# A7_JTAG_CONFIG_-.net
KiCad netlist of a schematic drawn in Altium Designer
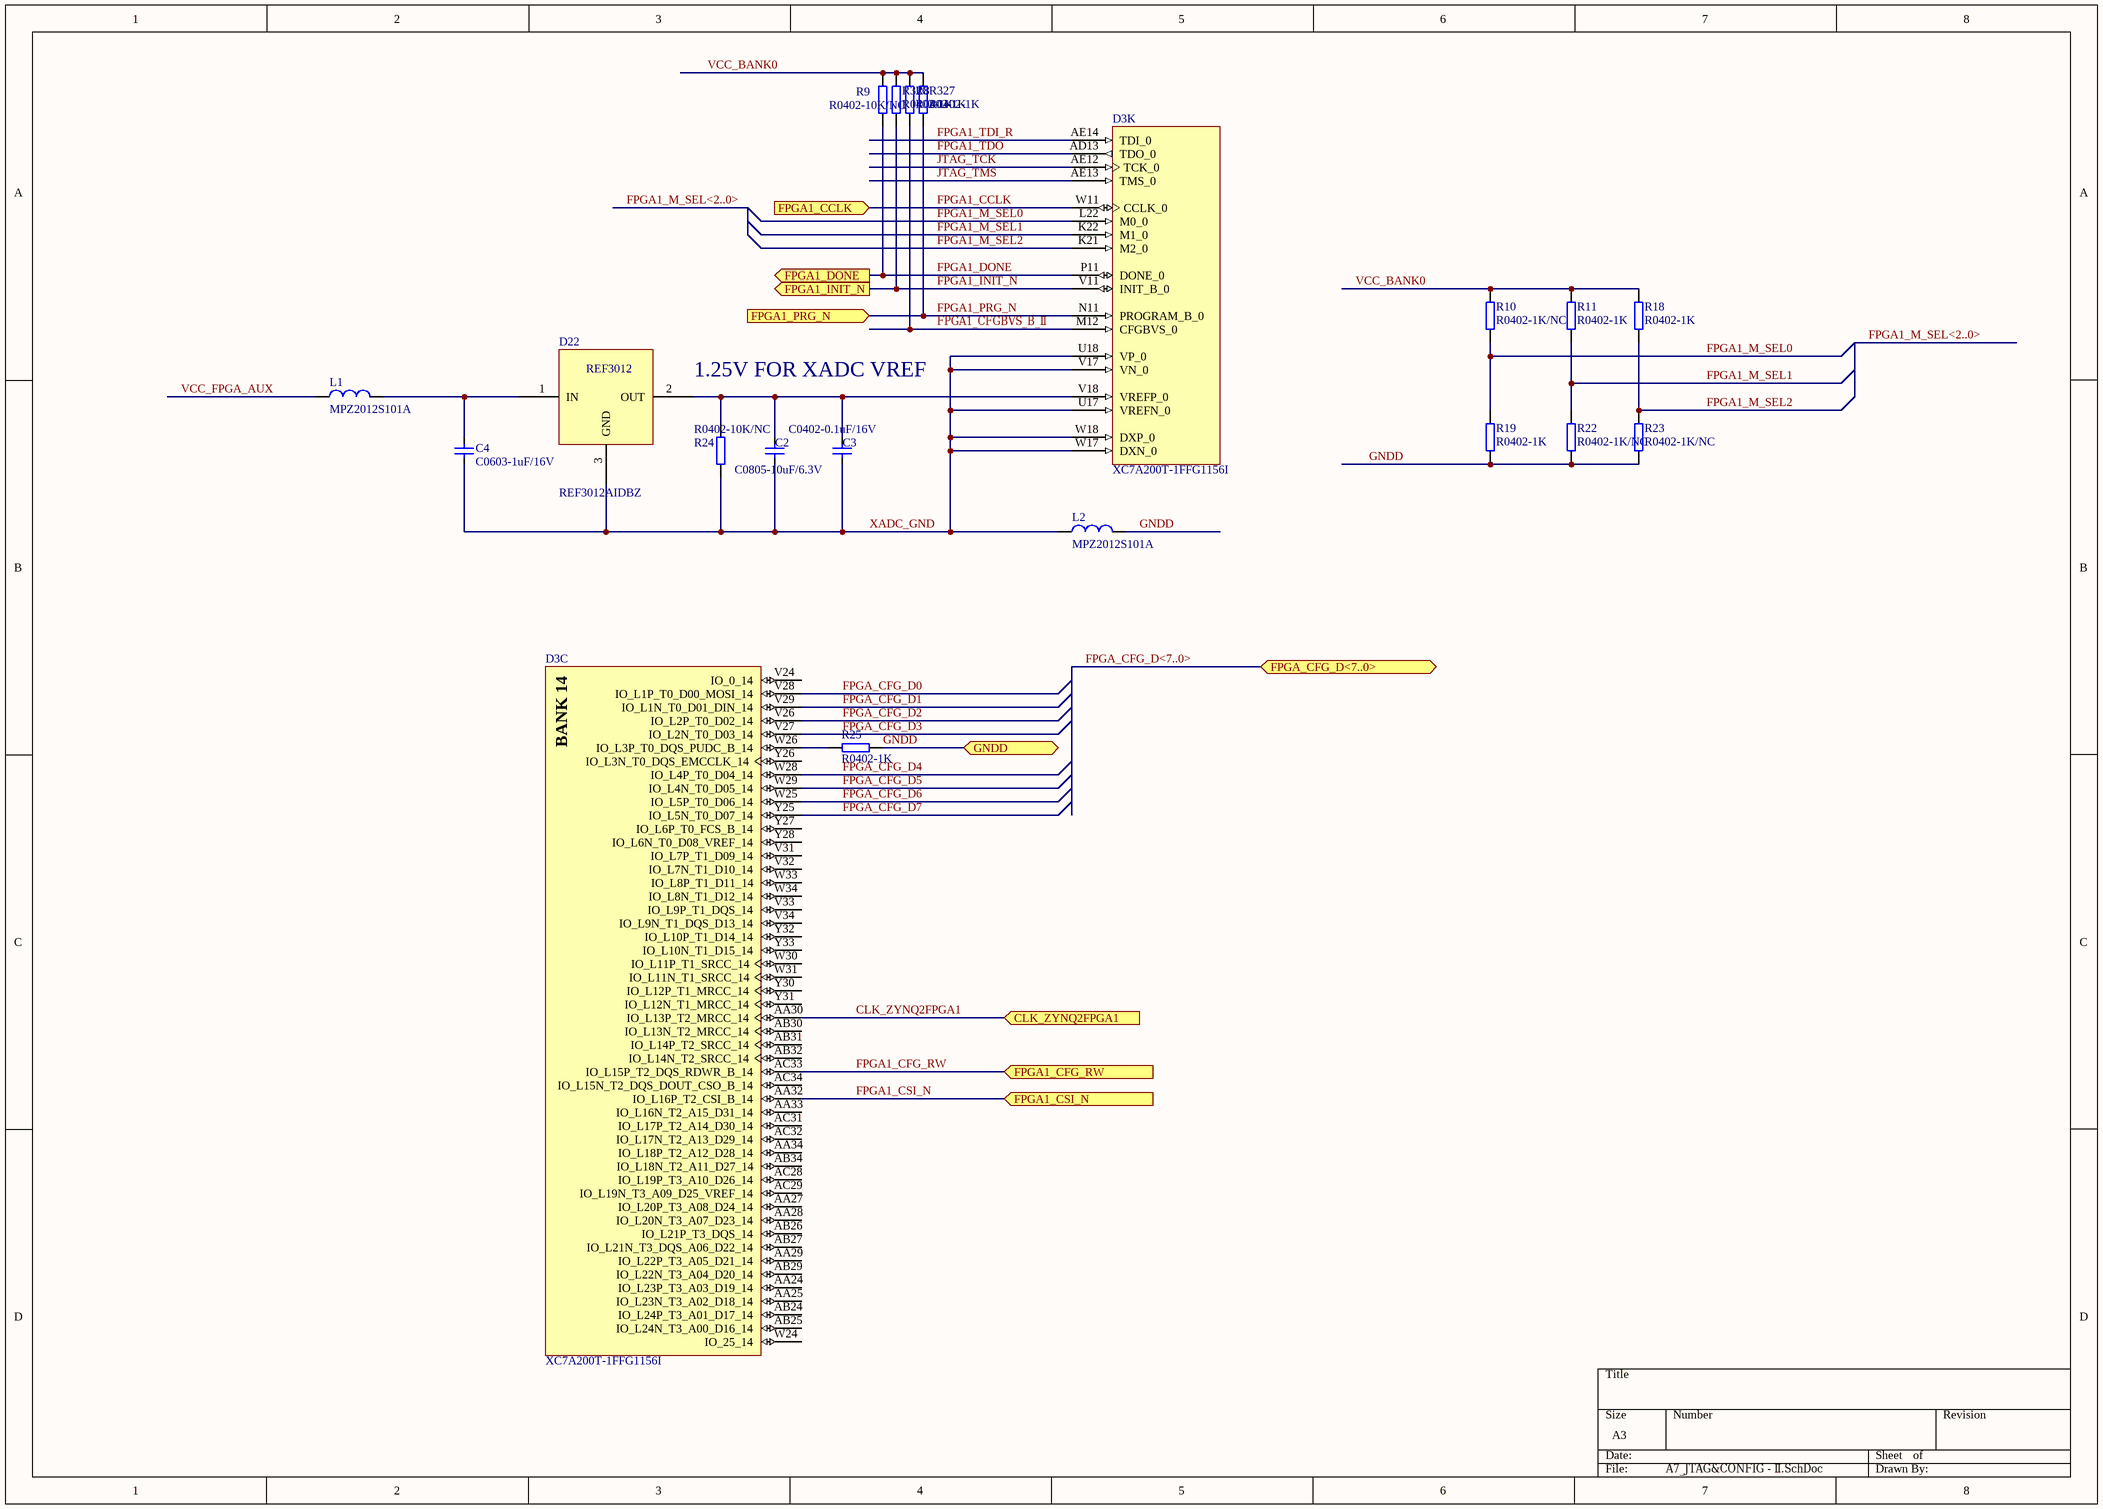
[diagram p0: A7_JTAG&CONFIG - Ⅱ.SchDoc]

(export (version "E")
  (design (tool "Eeschema 10.0.6"))
  (components
    (comp (ref "C2")
      (value "C0805-10uF/6.3V")
      (footprint "C0805")
      (fields (field (name "SCHEMATIC_PART") "CAP"))
      (libsource (lib "Database_Libs1") (part "CAP"))
    )
    (comp (ref "C3")
      (value "C0402-0.1uF/16V")
      (footprint "C0402")
      (description "X7R")
      (fields (field (name "SCHEMATIC_PART") "CAP") (field (name "MANUFACTURER") "SAMSUNG"))
      (libsource (lib "Database_Libs1") (part "CAP"))
    )
    (comp (ref "C4")
      (value "C0603-1uF/16V")
      (footprint "C0603")
      (description "X7R")
      (fields (field (name "SCHEMATIC_PART") "CAP"))
      (libsource (lib "Database_Libs1") (part "CAP"))
    )
    (comp (ref "D3")
      (value "XC7A200T-1FFG1156I")
      (footprint "FFG1156")
      (description "Artix-7 FPGA, 500 User I/Os, 16 GTP, 1156-Ball BGA, Speed Grade 1, Industrial Grade, Pb-Free")
      (fields (field (name "GENERIC PART NUMBER") "XC7A200T") (field (name "MANUFACTURER") "Xilinx"))
      (libsource (lib "Xilinx Artix-7") (part "XC7A200T-1FFG1156I"))
    )
    (comp (ref "D22")
      (value "REF3012AIDBZ")
      (footprint "SOT-23")
      (libsource (lib "SCHLIB1") (part "REF3012"))
    )
    (comp (ref "L1")
      (value "MPZ2012S101A")
      (footprint "R0805")
      (fields (field (name "SCHEMATIC_PART") "BEAD") (field (name "MANUFACTURER") "TDK"))
      (libsource (lib "Database_Libs1") (part "BEAD"))
    )
    (comp (ref "L2")
      (value "MPZ2012S101A")
      (footprint "R0805")
      (fields (field (name "SCHEMATIC_PART") "BEAD") (field (name "MANUFACTURER") "TDK"))
      (libsource (lib "Database_Libs1") (part "BEAD"))
    )
    (comp (ref "R8")
      (value "R0402-1K")
      (footprint "R0402")
      (fields (field (name "SCHEMATIC_PART") "RES") (field (name "MANUFACTURER") "SAMSUNG"))
      (libsource (lib "Database_Libs1") (part "RES"))
    )
    (comp (ref "R9")
      (value "R0402-10K/NC")
      (footprint "R0402")
      (fields (field (name "SCHEMATIC_PART") "RES") (field (name "MANUFACTURER") "SAMSUNG"))
      (libsource (lib "Database_Libs1") (part "RES"))
    )
    (comp (ref "R10")
      (value "R0402-1K/NC")
      (footprint "R0402")
      (fields (field (name "SCHEMATIC_PART") "RES") (field (name "MANUFACTURER") "SAMSUNG"))
      (libsource (lib "Database_Libs1") (part "RES"))
    )
    (comp (ref "R11")
      (value "R0402-1K")
      (footprint "R0402")
      (fields (field (name "SCHEMATIC_PART") "RES") (field (name "MANUFACTURER") "SAMSUNG"))
      (libsource (lib "Database_Libs1") (part "RES"))
    )
    (comp (ref "R18")
      (value "R0402-1K")
      (footprint "R0402")
      (fields (field (name "SCHEMATIC_PART") "RES") (field (name "MANUFACTURER") "SAMSUNG"))
      (libsource (lib "Database_Libs1") (part "RES"))
    )
    (comp (ref "R19")
      (value "R0402-1K")
      (footprint "R0402")
      (fields (field (name "SCHEMATIC_PART") "RES") (field (name "MANUFACTURER") "SAMSUNG"))
      (libsource (lib "Database_Libs1") (part "RES"))
    )
    (comp (ref "R22")
      (value "R0402-1K/NC")
      (footprint "R0402")
      (fields (field (name "SCHEMATIC_PART") "RES") (field (name "MANUFACTURER") "SAMSUNG"))
      (libsource (lib "Database_Libs1") (part "RES"))
    )
    (comp (ref "R23")
      (value "R0402-1K/NC")
      (footprint "R0402")
      (fields (field (name "SCHEMATIC_PART") "RES") (field (name "MANUFACTURER") "SAMSUNG"))
      (libsource (lib "Database_Libs1") (part "RES"))
    )
    (comp (ref "R24")
      (value "R0402-10K/NC")
      (footprint "R0402")
      (fields (field (name "SCHEMATIC_PART") "RES") (field (name "MANUFACTURER") "SAMSUNG"))
      (libsource (lib "Database_Libs1") (part "RES"))
    )
    (comp (ref "R25")
      (value "R0402-1K")
      (footprint "R0402")
      (fields (field (name "SCHEMATIC_PART") "RES") (field (name "MANUFACTURER") "SAMSUNG"))
      (libsource (lib "Database_Libs1") (part "RES"))
    )
    (comp (ref "R326")
      (value "R0402-1K")
      (footprint "R0402")
      (fields (field (name "SCHEMATIC_PART") "RES") (field (name "MANUFACTURER") "SAMSUNG"))
      (libsource (lib "Database_Libs1") (part "RES"))
    )
    (comp (ref "R327")
      (value "R0402-1K")
      (footprint "R0402")
      (fields (field (name "SCHEMATIC_PART") "RES") (field (name "MANUFACTURER") "SAMSUNG"))
      (libsource (lib "Database_Libs1") (part "RES"))
    )
  )
  (nets
    (net (code "3") (name "/CLK_ZYNQ2FPGA1") (class "Default")
      (node (ref "D3") (pin "AA30") (pinfunction "IO_L13P_T2_MRCC_14_AA30") (pintype "bidirectional"))
    )
    (net (code "4") (name "/FPGA1_CCLK") (class "Default")
      (node (ref "D3") (pin "W11") (pinfunction "CCLK_0_W11") (pintype "bidirectional"))
    )
    (net (code "5") (name "/FPGA1_CFGBVS_B_Ⅱ") (class "Default")
      (node (ref "D3") (pin "M12") (pinfunction "CFGBVS_0_M12") (pintype "input"))
      (node (ref "R8") (pin "1") (pintype "passive"))
    )
    (net (code "6") (name "/FPGA1_CFG_RW") (class "Default")
      (node (ref "D3") (pin "AC33") (pinfunction "IO_L15P_T2_DQS_RDWR_B_14_AC33") (pintype "bidirectional"))
    )
    (net (code "7") (name "/FPGA1_CSI_N") (class "Default")
      (node (ref "D3") (pin "AA32") (pinfunction "IO_L16P_T2_CSI_B_14_AA32") (pintype "bidirectional"))
    )
    (net (code "8") (name "/FPGA1_DONE") (class "Default")
      (node (ref "D3") (pin "P11") (pinfunction "DONE_0_P11") (pintype "bidirectional"))
      (node (ref "R9") (pin "1") (pintype "passive"))
    )
    (net (code "9") (name "/FPGA1_INIT_N") (class "Default")
      (node (ref "D3") (pin "V11") (pinfunction "INIT_B_0_V11") (pintype "bidirectional"))
      (node (ref "R326") (pin "1") (pintype "passive"))
    )
    (net (code "10") (name "/FPGA1_M_SEL0") (class "Default")
      (node (ref "D3") (pin "L22") (pinfunction "M0_0_L22") (pintype "input"))
      (node (ref "R10") (pin "1") (pintype "passive"))
      (node (ref "R19") (pin "2") (pintype "passive"))
    )
    (net (code "11") (name "/FPGA1_M_SEL1") (class "Default")
      (node (ref "D3") (pin "K22") (pinfunction "M1_0_K22") (pintype "input"))
      (node (ref "R11") (pin "1") (pintype "passive"))
      (node (ref "R22") (pin "2") (pintype "passive"))
    )
    (net (code "12") (name "/FPGA1_M_SEL2") (class "Default")
      (node (ref "D3") (pin "K21") (pinfunction "M2_0_K21") (pintype "input"))
      (node (ref "R18") (pin "1") (pintype "passive"))
      (node (ref "R23") (pin "2") (pintype "passive"))
    )
    (net (code "13") (name "/FPGA1_PRG_N") (class "Default")
      (node (ref "D3") (pin "N11") (pinfunction "PROGRAM_B_0_N11") (pintype "input"))
      (node (ref "R327") (pin "1") (pintype "passive"))
    )
    (net (code "14") (name "/FPGA1_TDI_R") (class "Default")
      (node (ref "D3") (pin "AE14") (pinfunction "TDI_0_AE14") (pintype "input"))
    )
    (net (code "15") (name "/FPGA1_TDO") (class "Default")
      (node (ref "D3") (pin "AD13") (pinfunction "TDO_0_AD13") (pintype "output"))
    )
    (net (code "16") (name "/FPGA_CFG_D0") (class "Default")
      (node (ref "D3") (pin "V28") (pinfunction "IO_L1P_T0_D00_MOSI_14_V28") (pintype "bidirectional"))
    )
    (net (code "17") (name "/FPGA_CFG_D1") (class "Default")
      (node (ref "D3") (pin "V29") (pinfunction "IO_L1N_T0_D01_DIN_14_V29") (pintype "bidirectional"))
    )
    (net (code "18") (name "/FPGA_CFG_D2") (class "Default")
      (node (ref "D3") (pin "V26") (pinfunction "IO_L2P_T0_D02_14_V26") (pintype "bidirectional"))
    )
    (net (code "19") (name "/FPGA_CFG_D3") (class "Default")
      (node (ref "D3") (pin "V27") (pinfunction "IO_L2N_T0_D03_14_V27") (pintype "bidirectional"))
    )
    (net (code "20") (name "/FPGA_CFG_D4") (class "Default")
      (node (ref "D3") (pin "W28") (pinfunction "IO_L4P_T0_D04_14_W28") (pintype "bidirectional"))
    )
    (net (code "21") (name "/FPGA_CFG_D5") (class "Default")
      (node (ref "D3") (pin "W29") (pinfunction "IO_L4N_T0_D05_14_W29") (pintype "bidirectional"))
    )
    (net (code "22") (name "/FPGA_CFG_D6") (class "Default")
      (node (ref "D3") (pin "W25") (pinfunction "IO_L5P_T0_D06_14_W25") (pintype "bidirectional"))
    )
    (net (code "23") (name "/FPGA_CFG_D7") (class "Default")
      (node (ref "D3") (pin "Y25") (pinfunction "IO_L5N_T0_D07_14_Y25") (pintype "bidirectional"))
    )
    (net (code "24") (name "/GNDD") (class "Default")
      (node (ref "L2") (pin "2") (pinfunction "2_2") (pintype "passive"))
      (node (ref "R19") (pin "1") (pintype "passive"))
      (node (ref "R22") (pin "1") (pintype "passive"))
      (node (ref "R23") (pin "1") (pintype "passive"))
      (node (ref "R25") (pin "1") (pintype "passive"))
    )
    (net (code "25") (name "/JTAG_TCK") (class "Default")
      (node (ref "D3") (pin "AE12") (pinfunction "TCK_0_AE12") (pintype "input"))
    )
    (net (code "26") (name "/JTAG_TMS") (class "Default")
      (node (ref "D3") (pin "AE13") (pinfunction "TMS_0_AE13") (pintype "input"))
    )
    (net (code "27") (name "/VCC_BANK0") (class "Default")
      (node (ref "R10") (pin "2") (pintype "passive"))
      (node (ref "R11") (pin "2") (pintype "passive"))
      (node (ref "R18") (pin "2") (pintype "passive"))
      (node (ref "R326") (pin "2") (pintype "passive"))
      (node (ref "R327") (pin "2") (pintype "passive"))
      (node (ref "R8") (pin "2") (pintype "passive"))
      (node (ref "R9") (pin "2") (pintype "passive"))
    )
    (net (code "28") (name "/VCC_FPGA_AUX") (class "Default")
      (node (ref "L1") (pin "1") (pinfunction "1_1") (pintype "passive"))
    )
    (net (code "29") (name "/XADC_GND") (class "Default")
      (node (ref "C2") (pin "2") (pinfunction "2_2") (pintype "passive"))
      (node (ref "C3") (pin "2") (pinfunction "2_2") (pintype "passive"))
      (node (ref "C4") (pin "2") (pinfunction "2_2") (pintype "passive"))
      (node (ref "D22") (pin "3") (pinfunction "GND_3") (pintype "passive"))
      (node (ref "D3") (pin "U17") (pinfunction "VREFN_0_U17") (pintype "input"))
      (node (ref "D3") (pin "U18") (pinfunction "VP_0_U18") (pintype "input"))
      (node (ref "D3") (pin "V17") (pinfunction "VN_0_V17") (pintype "input"))
      (node (ref "D3") (pin "W17") (pinfunction "DXN_0_W17") (pintype "input"))
      (node (ref "D3") (pin "W18") (pinfunction "DXP_0_W18") (pintype "input"))
      (node (ref "L2") (pin "1") (pinfunction "1_1") (pintype "passive"))
      (node (ref "R24") (pin "2") (pintype "passive"))
    )
    (net (code "32") (name "Net-(D3C-IO_L3P_T0_DQS_PUDC_B_14)") (class "Default")
      (node (ref "D3") (pin "W26") (pinfunction "IO_L3P_T0_DQS_PUDC_B_14_W26") (pintype "bidirectional"))
      (node (ref "R25") (pin "2") (pintype "passive"))
    )
    (net (code "33") (name "Net-(D22-IN)") (class "Default")
      (node (ref "C4") (pin "1") (pinfunction "1_1") (pintype "passive"))
      (node (ref "D22") (pin "1") (pinfunction "IN_1") (pintype "passive"))
      (node (ref "L1") (pin "2") (pinfunction "2_2") (pintype "passive"))
    )
    (net (code "34") (name "Net-(D22-OUT)") (class "Default")
      (node (ref "C2") (pin "1") (pinfunction "1_1") (pintype "passive"))
      (node (ref "C3") (pin "1") (pinfunction "1_1") (pintype "passive"))
      (node (ref "D22") (pin "2") (pinfunction "OUT_2") (pintype "passive"))
      (node (ref "D3") (pin "V18") (pinfunction "VREFP_0_V18") (pintype "input"))
      (node (ref "R24") (pin "1") (pintype "passive"))
    )
    (net (code "35") (name "unconnected-(D3C-IO_0_14-PadV24)") (class "Default")
      (node (ref "D3") (pin "V24") (pinfunction "IO_0_14_V24") (pintype "bidirectional"))
    )
    (net (code "36") (name "unconnected-(D3C-IO_25_14-PadW24)") (class "Default")
      (node (ref "D3") (pin "W24") (pinfunction "IO_25_14_W24") (pintype "bidirectional"))
    )
    (net (code "37") (name "unconnected-(D3C-IO_L3N_T0_DQS_EMCCLK_14-PadY26)") (class "Default")
      (node (ref "D3") (pin "Y26") (pinfunction "IO_L3N_T0_DQS_EMCCLK_14_Y26") (pintype "bidirectional"))
    )
    (net (code "38") (name "unconnected-(D3C-IO_L6N_T0_D08_VREF_14-PadY28)") (class "Default")
      (node (ref "D3") (pin "Y28") (pinfunction "IO_L6N_T0_D08_VREF_14_Y28") (pintype "bidirectional"))
    )
    (net (code "39") (name "unconnected-(D3C-IO_L6P_T0_FCS_B_14-PadY27)") (class "Default")
      (node (ref "D3") (pin "Y27") (pinfunction "IO_L6P_T0_FCS_B_14_Y27") (pintype "bidirectional"))
    )
    (net (code "40") (name "unconnected-(D3C-IO_L7N_T1_D10_14-PadV32)") (class "Default")
      (node (ref "D3") (pin "V32") (pinfunction "IO_L7N_T1_D10_14_V32") (pintype "bidirectional"))
    )
    (net (code "41") (name "unconnected-(D3C-IO_L7P_T1_D09_14-PadV31)") (class "Default")
      (node (ref "D3") (pin "V31") (pinfunction "IO_L7P_T1_D09_14_V31") (pintype "bidirectional"))
    )
    (net (code "42") (name "unconnected-(D3C-IO_L8N_T1_D12_14-PadW34)") (class "Default")
      (node (ref "D3") (pin "W34") (pinfunction "IO_L8N_T1_D12_14_W34") (pintype "bidirectional"))
    )
    (net (code "43") (name "unconnected-(D3C-IO_L8P_T1_D11_14-PadW33)") (class "Default")
      (node (ref "D3") (pin "W33") (pinfunction "IO_L8P_T1_D11_14_W33") (pintype "bidirectional"))
    )
    (net (code "44") (name "unconnected-(D3C-IO_L9N_T1_DQS_D13_14-PadV34)") (class "Default")
      (node (ref "D3") (pin "V34") (pinfunction "IO_L9N_T1_DQS_D13_14_V34") (pintype "bidirectional"))
    )
    (net (code "45") (name "unconnected-(D3C-IO_L9P_T1_DQS_14-PadV33)") (class "Default")
      (node (ref "D3") (pin "V33") (pinfunction "IO_L9P_T1_DQS_14_V33") (pintype "bidirectional"))
    )
    (net (code "46") (name "unconnected-(D3C-IO_L10N_T1_D15_14-PadY33)") (class "Default")
      (node (ref "D3") (pin "Y33") (pinfunction "IO_L10N_T1_D15_14_Y33") (pintype "bidirectional"))
    )
    (net (code "47") (name "unconnected-(D3C-IO_L10P_T1_D14_14-PadY32)") (class "Default")
      (node (ref "D3") (pin "Y32") (pinfunction "IO_L10P_T1_D14_14_Y32") (pintype "bidirectional"))
    )
    (net (code "48") (name "unconnected-(D3C-IO_L11N_T1_SRCC_14-PadW31)") (class "Default")
      (node (ref "D3") (pin "W31") (pinfunction "IO_L11N_T1_SRCC_14_W31") (pintype "bidirectional"))
    )
    (net (code "49") (name "unconnected-(D3C-IO_L11P_T1_SRCC_14-PadW30)") (class "Default")
      (node (ref "D3") (pin "W30") (pinfunction "IO_L11P_T1_SRCC_14_W30") (pintype "bidirectional"))
    )
    (net (code "50") (name "unconnected-(D3C-IO_L12N_T1_MRCC_14-PadY31)") (class "Default")
      (node (ref "D3") (pin "Y31") (pinfunction "IO_L12N_T1_MRCC_14_Y31") (pintype "bidirectional"))
    )
    (net (code "51") (name "unconnected-(D3C-IO_L12P_T1_MRCC_14-PadY30)") (class "Default")
      (node (ref "D3") (pin "Y30") (pinfunction "IO_L12P_T1_MRCC_14_Y30") (pintype "bidirectional"))
    )
    (net (code "52") (name "unconnected-(D3C-IO_L13N_T2_MRCC_14-PadAB30)") (class "Default")
      (node (ref "D3") (pin "AB30") (pinfunction "IO_L13N_T2_MRCC_14_AB30") (pintype "bidirectional"))
    )
    (net (code "53") (name "unconnected-(D3C-IO_L14N_T2_SRCC_14-PadAB32)") (class "Default")
      (node (ref "D3") (pin "AB32") (pinfunction "IO_L14N_T2_SRCC_14_AB32") (pintype "bidirectional"))
    )
    (net (code "54") (name "unconnected-(D3C-IO_L14P_T2_SRCC_14-PadAB31)") (class "Default")
      (node (ref "D3") (pin "AB31") (pinfunction "IO_L14P_T2_SRCC_14_AB31") (pintype "bidirectional"))
    )
    (net (code "55") (name "unconnected-(D3C-IO_L15N_T2_DQS_DOUT_CSO_B_14-PadAC34)") (class "Default")
      (node (ref "D3") (pin "AC34") (pinfunction "IO_L15N_T2_DQS_DOUT_CSO_B_14_AC34") (pintype "bidirectional"))
    )
    (net (code "56") (name "unconnected-(D3C-IO_L16N_T2_A15_D31_14-PadAA33)") (class "Default")
      (node (ref "D3") (pin "AA33") (pinfunction "IO_L16N_T2_A15_D31_14_AA33") (pintype "bidirectional"))
    )
    (net (code "57") (name "unconnected-(D3C-IO_L17N_T2_A13_D29_14-PadAC32)") (class "Default")
      (node (ref "D3") (pin "AC32") (pinfunction "IO_L17N_T2_A13_D29_14_AC32") (pintype "bidirectional"))
    )
    (net (code "58") (name "unconnected-(D3C-IO_L17P_T2_A14_D30_14-PadAC31)") (class "Default")
      (node (ref "D3") (pin "AC31") (pinfunction "IO_L17P_T2_A14_D30_14_AC31") (pintype "bidirectional"))
    )
    (net (code "59") (name "unconnected-(D3C-IO_L18N_T2_A11_D27_14-PadAB34)") (class "Default")
      (node (ref "D3") (pin "AB34") (pinfunction "IO_L18N_T2_A11_D27_14_AB34") (pintype "bidirectional"))
    )
    (net (code "60") (name "unconnected-(D3C-IO_L18P_T2_A12_D28_14-PadAA34)") (class "Default")
      (node (ref "D3") (pin "AA34") (pinfunction "IO_L18P_T2_A12_D28_14_AA34") (pintype "bidirectional"))
    )
    (net (code "61") (name "unconnected-(D3C-IO_L19N_T3_A09_D25_VREF_14-PadAC29)") (class "Default")
      (node (ref "D3") (pin "AC29") (pinfunction "IO_L19N_T3_A09_D25_VREF_14_AC29") (pintype "bidirectional"))
    )
    (net (code "62") (name "unconnected-(D3C-IO_L19P_T3_A10_D26_14-PadAC28)") (class "Default")
      (node (ref "D3") (pin "AC28") (pinfunction "IO_L19P_T3_A10_D26_14_AC28") (pintype "bidirectional"))
    )
    (net (code "63") (name "unconnected-(D3C-IO_L20N_T3_A07_D23_14-PadAA28)") (class "Default")
      (node (ref "D3") (pin "AA28") (pinfunction "IO_L20N_T3_A07_D23_14_AA28") (pintype "bidirectional"))
    )
    (net (code "64") (name "unconnected-(D3C-IO_L20P_T3_A08_D24_14-PadAA27)") (class "Default")
      (node (ref "D3") (pin "AA27") (pinfunction "IO_L20P_T3_A08_D24_14_AA27") (pintype "bidirectional"))
    )
    (net (code "65") (name "unconnected-(D3C-IO_L21N_T3_DQS_A06_D22_14-PadAB27)") (class "Default")
      (node (ref "D3") (pin "AB27") (pinfunction "IO_L21N_T3_DQS_A06_D22_14_AB27") (pintype "bidirectional"))
    )
    (net (code "66") (name "unconnected-(D3C-IO_L21P_T3_DQS_14-PadAB26)") (class "Default")
      (node (ref "D3") (pin "AB26") (pinfunction "IO_L21P_T3_DQS_14_AB26") (pintype "bidirectional"))
    )
    (net (code "67") (name "unconnected-(D3C-IO_L22N_T3_A04_D20_14-PadAB29)") (class "Default")
      (node (ref "D3") (pin "AB29") (pinfunction "IO_L22N_T3_A04_D20_14_AB29") (pintype "bidirectional"))
    )
    (net (code "68") (name "unconnected-(D3C-IO_L22P_T3_A05_D21_14-PadAA29)") (class "Default")
      (node (ref "D3") (pin "AA29") (pinfunction "IO_L22P_T3_A05_D21_14_AA29") (pintype "bidirectional"))
    )
    (net (code "69") (name "unconnected-(D3C-IO_L23N_T3_A02_D18_14-PadAA25)") (class "Default")
      (node (ref "D3") (pin "AA25") (pinfunction "IO_L23N_T3_A02_D18_14_AA25") (pintype "bidirectional"))
    )
    (net (code "70") (name "unconnected-(D3C-IO_L23P_T3_A03_D19_14-PadAA24)") (class "Default")
      (node (ref "D3") (pin "AA24") (pinfunction "IO_L23P_T3_A03_D19_14_AA24") (pintype "bidirectional"))
    )
    (net (code "71") (name "unconnected-(D3C-IO_L24N_T3_A00_D16_14-PadAB25)") (class "Default")
      (node (ref "D3") (pin "AB25") (pinfunction "IO_L24N_T3_A00_D16_14_AB25") (pintype "bidirectional"))
    )
    (net (code "72") (name "unconnected-(D3C-IO_L24P_T3_A01_D17_14-PadAB24)") (class "Default")
      (node (ref "D3") (pin "AB24") (pinfunction "IO_L24P_T3_A01_D17_14_AB24") (pintype "bidirectional"))
    )
  )
)
